# relay-shield.net
KiCad netlist of a schematic drawn in EAGLE
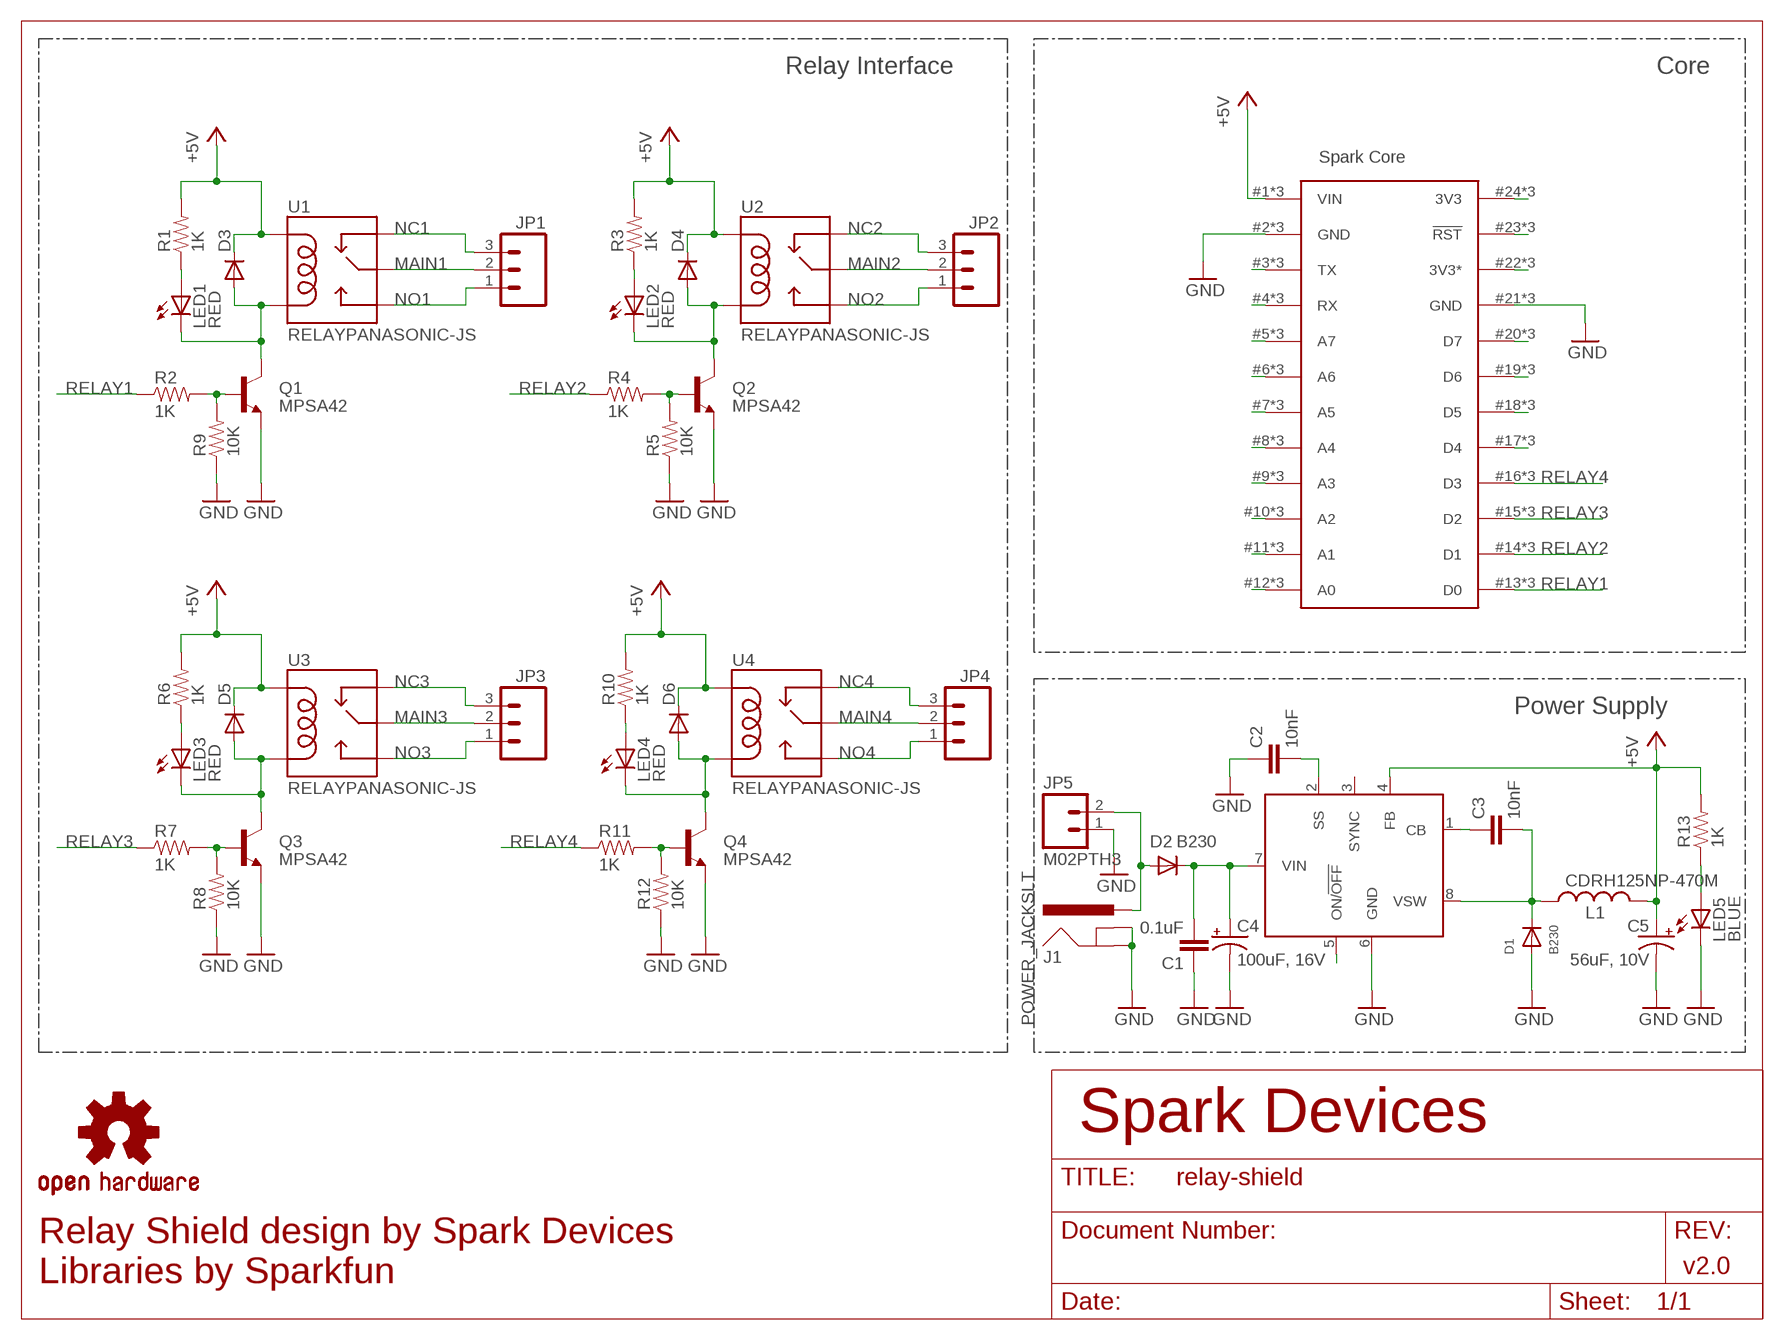
[diagram p0: schematic, sheet 1]

(export (version "E")
  (design (tool "Eeschema 10.0.6"))
  (components
    (comp (ref "C1")
      (value "0.1uF")
      (footprint "eagle-import:0603-CAP")
      (libsource (lib "eagle-import") (part "0.1UF-25V-5%(0603)"))
    )
    (comp (ref "C2")
      (value "10nF")
      (footprint "eagle-import:0603-CAP")
      (libsource (lib "eagle-import") (part "CAP0603-CAP"))
    )
    (comp (ref "C3")
      (value "10nF")
      (footprint "eagle-import:0603-CAP")
      (libsource (lib "eagle-import") (part "CAP0603-CAP"))
    )
    (comp (ref "C4")
      (value "100uF, 16V")
      (footprint "eagle-import:PANASONIC_D")
      (libsource (lib "eagle-import") (part "CAP_POLD"))
    )
    (comp (ref "C5")
      (value "56uF, 10V")
      (footprint "eagle-import:PANASONIC_D")
      (libsource (lib "eagle-import") (part "CAP_POLD"))
    )
    (comp (ref "D1")
      (value "B230")
      (footprint "eagle-import:SMADIODE")
      (libsource (lib "eagle-import") (part "DIODESMA"))
    )
    (comp (ref "D2")
      (value "B230")
      (footprint "eagle-import:SMADIODE")
      (libsource (lib "eagle-import") (part "DIODESMA"))
    )
    (comp (ref "D3")
      (value "DIODE-SOD123")
      (footprint "eagle-import:SOD123")
      (libsource (lib "eagle-import") (part "DIODE-SOD123"))
    )
    (comp (ref "D4")
      (value "DIODE-SOD123")
      (footprint "eagle-import:SOD123")
      (libsource (lib "eagle-import") (part "DIODE-SOD123"))
    )
    (comp (ref "D5")
      (value "DIODE-SOD123")
      (footprint "eagle-import:SOD123")
      (libsource (lib "eagle-import") (part "DIODE-SOD123"))
    )
    (comp (ref "D6")
      (value "DIODE-SOD123")
      (footprint "eagle-import:SOD123")
      (libsource (lib "eagle-import") (part "DIODE-SOD123"))
    )
    (comp (ref "J1")
      (value "POWER_JACKSLT")
      (footprint "eagle-import:POWER_JACK_SLOT")
      (libsource (lib "eagle-import") (part "POWER_JACKSLT"))
    )
    (comp (ref "JP1")
      (value "M03-SCREW-5MM")
      (footprint "eagle-import:SCREWTERMINAL-5MM-3")
      (libsource (lib "eagle-import") (part "M03-SCREW-5MM"))
    )
    (comp (ref "JP2")
      (value "M03-SCREW-5MM")
      (footprint "eagle-import:SCREWTERMINAL-5MM-3")
      (libsource (lib "eagle-import") (part "M03-SCREW-5MM"))
    )
    (comp (ref "JP3")
      (value "M03-SCREW-5MM")
      (footprint "eagle-import:SCREWTERMINAL-5MM-3")
      (libsource (lib "eagle-import") (part "M03-SCREW-5MM"))
    )
    (comp (ref "JP4")
      (value "M03-SCREW-5MM")
      (footprint "eagle-import:SCREWTERMINAL-5MM-3")
      (libsource (lib "eagle-import") (part "M03-SCREW-5MM"))
    )
    (comp (ref "JP5")
      (value "M02PTH3")
      (footprint "eagle-import:1X02_LONGPADS")
      (libsource (lib "eagle-import") (part "M02PTH3"))
    )
    (comp (ref "L1")
      (value "CDRH125NP-470M")
      (footprint "eagle-import:CDRH125")
      (libsource (lib "eagle-import") (part "INDUCTORPWR"))
    )
    (comp (ref "LED1")
      (value "RED")
      (footprint "eagle-import:LED-0603")
      (libsource (lib "eagle-import") (part "LED0603"))
    )
    (comp (ref "LED2")
      (value "RED")
      (footprint "eagle-import:LED-0603")
      (libsource (lib "eagle-import") (part "LED0603"))
    )
    (comp (ref "LED3")
      (value "RED")
      (footprint "eagle-import:LED-0603")
      (libsource (lib "eagle-import") (part "LED0603"))
    )
    (comp (ref "LED4")
      (value "RED")
      (footprint "eagle-import:LED-0603")
      (libsource (lib "eagle-import") (part "LED0603"))
    )
    (comp (ref "LED5")
      (value "BLUE")
      (footprint "eagle-import:LED-0603")
      (libsource (lib "eagle-import") (part "LED0603"))
    )
    (comp (ref "LOGO1")
      (value "OSHW-LOGOM")
      (footprint "eagle-import:OSHW-LOGO-M")
      (libsource (lib "eagle-import") (part "OSHW-LOGOM"))
    )
    (comp (ref "Q1")
      (value "MPSA42")
      (footprint "eagle-import:SOT23")
      (libsource (lib "eagle-import") (part "TRANSISTOR_NPNMPSA42"))
    )
    (comp (ref "Q2")
      (value "MPSA42")
      (footprint "eagle-import:SOT23")
      (libsource (lib "eagle-import") (part "TRANSISTOR_NPNMPSA42"))
    )
    (comp (ref "Q3")
      (value "MPSA42")
      (footprint "eagle-import:SOT23")
      (libsource (lib "eagle-import") (part "TRANSISTOR_NPNMPSA42"))
    )
    (comp (ref "Q4")
      (value "MPSA42")
      (footprint "eagle-import:SOT23")
      (libsource (lib "eagle-import") (part "TRANSISTOR_NPNMPSA42"))
    )
    (comp (ref "R1")
      (value "1K")
      (footprint "eagle-import:0603-RES")
      (libsource (lib "eagle-import") (part "RESISTOR0603-RES"))
    )
    (comp (ref "R2")
      (value "1K")
      (footprint "eagle-import:0603-RES")
      (libsource (lib "eagle-import") (part "RESISTOR0603-RES"))
    )
    (comp (ref "R3")
      (value "1K")
      (footprint "eagle-import:0603-RES")
      (libsource (lib "eagle-import") (part "RESISTOR0603-RES"))
    )
    (comp (ref "R4")
      (value "1K")
      (footprint "eagle-import:0603-RES")
      (libsource (lib "eagle-import") (part "RESISTOR0603-RES"))
    )
    (comp (ref "R5")
      (value "10K")
      (footprint "eagle-import:0603-RES")
      (libsource (lib "eagle-import") (part "RESISTOR0603-RES"))
    )
    (comp (ref "R6")
      (value "1K")
      (footprint "eagle-import:0603-RES")
      (libsource (lib "eagle-import") (part "RESISTOR0603-RES"))
    )
    (comp (ref "R7")
      (value "1K")
      (footprint "eagle-import:0603-RES")
      (libsource (lib "eagle-import") (part "RESISTOR0603-RES"))
    )
    (comp (ref "R8")
      (value "10K")
      (footprint "eagle-import:0603-RES")
      (libsource (lib "eagle-import") (part "RESISTOR0603-RES"))
    )
    (comp (ref "R9")
      (value "10K")
      (footprint "eagle-import:0603-RES")
      (libsource (lib "eagle-import") (part "RESISTOR0603-RES"))
    )
    (comp (ref "R10")
      (value "1K")
      (footprint "eagle-import:0603-RES")
      (libsource (lib "eagle-import") (part "RESISTOR0603-RES"))
    )
    (comp (ref "R11")
      (value "1K")
      (footprint "eagle-import:0603-RES")
      (libsource (lib "eagle-import") (part "RESISTOR0603-RES"))
    )
    (comp (ref "R12")
      (value "10K")
      (footprint "eagle-import:0603-RES")
      (libsource (lib "eagle-import") (part "RESISTOR0603-RES"))
    )
    (comp (ref "R13")
      (value "1K")
      (footprint "eagle-import:0603-RES")
      (libsource (lib "eagle-import") (part "RESISTOR0603-RES"))
    )
    (comp (ref "U$1")
      (value "SPARK_CORE")
      (footprint "eagle-import:SPARK_CORE_STACKABLE")
      (libsource (lib "eagle-import") (part "SPARK_CORE"))
    )
    (comp (ref "U1")
      (value "RELAYPANASONIC-JS")
      (footprint "eagle-import:JS1-5V-F")
      (libsource (lib "eagle-import") (part "RELAYPANASONIC-JS"))
    )
    (comp (ref "U2")
      (value "RELAYPANASONIC-JS")
      (footprint "eagle-import:JS1-5V-F")
      (libsource (lib "eagle-import") (part "RELAYPANASONIC-JS"))
    )
    (comp (ref "U3")
      (value "RELAYPANASONIC-JS")
      (footprint "eagle-import:JS1-5V-F")
      (libsource (lib "eagle-import") (part "RELAYPANASONIC-JS"))
    )
    (comp (ref "U4")
      (value "RELAYPANASONIC-JS")
      (footprint "eagle-import:JS1-5V-F")
      (libsource (lib "eagle-import") (part "RELAYPANASONIC-JS"))
    )
    (comp (ref "U5")
      (value "LM2672")
      (footprint "eagle-import:SO08")
      (libsource (lib "eagle-import") (part "LM2672"))
    )
  )
  (nets
    (net (code "1") (name "+5V") (class "Default")
      (node (ref "C5") (pin "+") (pinfunction "+_+") (pintype "passive"))
      (node (ref "D3") (pin "C") (pinfunction "C_C") (pintype "passive"))
      (node (ref "D4") (pin "C") (pinfunction "C_C") (pintype "passive"))
      (node (ref "D5") (pin "C") (pinfunction "C_C") (pintype "passive"))
      (node (ref "D6") (pin "C") (pinfunction "C_C") (pintype "passive"))
      (node (ref "L1") (pin "2") (pinfunction "2_2") (pintype "passive"))
      (node (ref "R1") (pin "2") (pinfunction "2_2") (pintype "passive"))
      (node (ref "R10") (pin "2") (pinfunction "2_2") (pintype "passive"))
      (node (ref "R13") (pin "2") (pinfunction "2_2") (pintype "passive"))
      (node (ref "R3") (pin "2") (pinfunction "2_2") (pintype "passive"))
      (node (ref "R6") (pin "2") (pinfunction "2_2") (pintype "passive"))
      (node (ref "U$1") (pin "#1") (pinfunction "VIN_#1") (pintype "power_in"))
      (node (ref "U$1") (pin "1") (pinfunction "VIN_1") (pintype "power_in"))
      (node (ref "U$1") (pin "@1") (pinfunction "VIN_@1") (pintype "power_in"))
      (node (ref "U1") (pin "COIL1") (pinfunction "COIL1_COIL1") (pintype "bidirectional"))
      (node (ref "U2") (pin "COIL1") (pinfunction "COIL1_COIL1") (pintype "bidirectional"))
      (node (ref "U3") (pin "COIL1") (pinfunction "COIL1_COIL1") (pintype "bidirectional"))
      (node (ref "U4") (pin "COIL1") (pinfunction "COIL1_COIL1") (pintype "bidirectional"))
      (node (ref "U5") (pin "4") (pinfunction "FB_4") (pintype "bidirectional"))
    )
    (net (code "2") (name "/MAIN1") (class "Default")
      (node (ref "JP1") (pin "2") (pinfunction "2_2") (pintype "passive"))
      (node (ref "U1") (pin "COMMON") (pinfunction "MAIN_COMMON") (pintype "bidirectional"))
    )
    (net (code "3") (name "/MAIN2") (class "Default")
      (node (ref "JP2") (pin "2") (pinfunction "2_2") (pintype "passive"))
      (node (ref "U2") (pin "COMMON") (pinfunction "MAIN_COMMON") (pintype "bidirectional"))
    )
    (net (code "4") (name "/MAIN3") (class "Default")
      (node (ref "JP3") (pin "2") (pinfunction "2_2") (pintype "passive"))
      (node (ref "U3") (pin "COMMON") (pinfunction "MAIN_COMMON") (pintype "bidirectional"))
    )
    (net (code "5") (name "/MAIN4") (class "Default")
      (node (ref "JP4") (pin "2") (pinfunction "2_2") (pintype "passive"))
      (node (ref "U4") (pin "COMMON") (pinfunction "MAIN_COMMON") (pintype "bidirectional"))
    )
    (net (code "6") (name "/NC1") (class "Default")
      (node (ref "JP1") (pin "3") (pinfunction "3_3") (pintype "passive"))
      (node (ref "U1") (pin "CLOSED") (pinfunction "NC_CLOSED") (pintype "bidirectional"))
    )
    (net (code "7") (name "/NC2") (class "Default")
      (node (ref "JP2") (pin "3") (pinfunction "3_3") (pintype "passive"))
      (node (ref "U2") (pin "CLOSED") (pinfunction "NC_CLOSED") (pintype "bidirectional"))
    )
    (net (code "8") (name "/NC3") (class "Default")
      (node (ref "JP3") (pin "3") (pinfunction "3_3") (pintype "passive"))
      (node (ref "U3") (pin "CLOSED") (pinfunction "NC_CLOSED") (pintype "bidirectional"))
    )
    (net (code "9") (name "/NC4") (class "Default")
      (node (ref "JP4") (pin "3") (pinfunction "3_3") (pintype "passive"))
      (node (ref "U4") (pin "CLOSED") (pinfunction "NC_CLOSED") (pintype "bidirectional"))
    )
    (net (code "10") (name "/NO1") (class "Default")
      (node (ref "JP1") (pin "1") (pinfunction "1_1") (pintype "passive"))
      (node (ref "U1") (pin "OPEN") (pinfunction "NO_OPEN") (pintype "bidirectional"))
    )
    (net (code "11") (name "/NO2") (class "Default")
      (node (ref "JP2") (pin "1") (pinfunction "1_1") (pintype "passive"))
      (node (ref "U2") (pin "OPEN") (pinfunction "NO_OPEN") (pintype "bidirectional"))
    )
    (net (code "12") (name "/NO3") (class "Default")
      (node (ref "JP3") (pin "1") (pinfunction "1_1") (pintype "passive"))
      (node (ref "U3") (pin "OPEN") (pinfunction "NO_OPEN") (pintype "bidirectional"))
    )
    (net (code "13") (name "/NO4") (class "Default")
      (node (ref "JP4") (pin "1") (pinfunction "1_1") (pintype "passive"))
      (node (ref "U4") (pin "OPEN") (pinfunction "NO_OPEN") (pintype "bidirectional"))
    )
    (net (code "14") (name "/RELAY1") (class "Default")
      (node (ref "R2") (pin "1") (pinfunction "1_1") (pintype "passive"))
      (node (ref "U$1") (pin "#13") (pinfunction "D0_#13") (pintype "bidirectional"))
      (node (ref "U$1") (pin "13") (pinfunction "D0_13") (pintype "bidirectional"))
      (node (ref "U$1") (pin "@13") (pinfunction "D0_@13") (pintype "bidirectional"))
    )
    (net (code "15") (name "/RELAY2") (class "Default")
      (node (ref "R4") (pin "1") (pinfunction "1_1") (pintype "passive"))
      (node (ref "U$1") (pin "#14") (pinfunction "D1_#14") (pintype "bidirectional"))
      (node (ref "U$1") (pin "14") (pinfunction "D1_14") (pintype "bidirectional"))
      (node (ref "U$1") (pin "@14") (pinfunction "D1_@14") (pintype "bidirectional"))
    )
    (net (code "16") (name "/RELAY3") (class "Default")
      (node (ref "R7") (pin "1") (pinfunction "1_1") (pintype "passive"))
      (node (ref "U$1") (pin "#15") (pinfunction "D2_#15") (pintype "bidirectional"))
      (node (ref "U$1") (pin "15") (pinfunction "D2_15") (pintype "bidirectional"))
      (node (ref "U$1") (pin "@15") (pinfunction "D2_@15") (pintype "bidirectional"))
    )
    (net (code "17") (name "/RELAY4") (class "Default")
      (node (ref "R11") (pin "1") (pinfunction "1_1") (pintype "passive"))
      (node (ref "U$1") (pin "#16") (pinfunction "D3_#16") (pintype "bidirectional"))
      (node (ref "U$1") (pin "16") (pinfunction "D3_16") (pintype "bidirectional"))
      (node (ref "U$1") (pin "@16") (pinfunction "D3_@16") (pintype "bidirectional"))
    )
    (net (code "18") (name "GND") (class "Default")
      (node (ref "C1") (pin "1") (pinfunction "1_1") (pintype "passive"))
      (node (ref "C2") (pin "1") (pinfunction "1_1") (pintype "passive"))
      (node (ref "C4") (pin "-") (pinfunction "-_-") (pintype "passive"))
      (node (ref "C5") (pin "-") (pinfunction "-_-") (pintype "passive"))
      (node (ref "D1") (pin "A") (pinfunction "A_A") (pintype "passive"))
      (node (ref "J1") (pin "GND@1") (pinfunction "GNDBREAK_GND@1") (pintype "bidirectional"))
      (node (ref "J1") (pin "GND@2") (pinfunction "GND_GND@2") (pintype "bidirectional"))
      (node (ref "JP5") (pin "1") (pinfunction "1_1") (pintype "passive"))
      (node (ref "LED5") (pin "C") (pinfunction "C_C") (pintype "passive"))
      (node (ref "Q1") (pin "2") (pinfunction "E_2") (pintype "passive"))
      (node (ref "Q2") (pin "2") (pinfunction "E_2") (pintype "passive"))
      (node (ref "Q3") (pin "2") (pinfunction "E_2") (pintype "passive"))
      (node (ref "Q4") (pin "2") (pinfunction "E_2") (pintype "passive"))
      (node (ref "R12") (pin "1") (pinfunction "1_1") (pintype "passive"))
      (node (ref "R5") (pin "1") (pinfunction "1_1") (pintype "passive"))
      (node (ref "R8") (pin "1") (pinfunction "1_1") (pintype "passive"))
      (node (ref "R9") (pin "1") (pinfunction "1_1") (pintype "passive"))
      (node (ref "U$1") (pin "#2") (pinfunction "GND_#2") (pintype "power_in"))
      (node (ref "U$1") (pin "#21") (pinfunction "GND_#21") (pintype "power_in"))
      (node (ref "U$1") (pin "2") (pinfunction "GND_2") (pintype "power_in"))
      (node (ref "U$1") (pin "21") (pinfunction "GND_21") (pintype "power_in"))
      (node (ref "U$1") (pin "@2") (pinfunction "GND_@2") (pintype "power_in"))
      (node (ref "U$1") (pin "@21") (pinfunction "GND_@21") (pintype "power_in"))
      (node (ref "U5") (pin "6") (pinfunction "GND_6") (pintype "power_in"))
    )
    (net (code "19") (name "Net-(D2-PadA)") (class "Default")
      (node (ref "D2") (pin "A") (pinfunction "A_A") (pintype "passive"))
      (node (ref "J1") (pin "PWR") (pinfunction "PWR_PWR") (pintype "bidirectional"))
      (node (ref "JP5") (pin "2") (pinfunction "2_2") (pintype "passive"))
    )
    (net (code "20") (name "Net-(LED1-PadA)") (class "Default")
      (node (ref "LED1") (pin "A") (pinfunction "A_A") (pintype "passive"))
      (node (ref "R1") (pin "1") (pinfunction "1_1") (pintype "passive"))
    )
    (net (code "21") (name "Net-(LED2-PadA)") (class "Default")
      (node (ref "LED2") (pin "A") (pinfunction "A_A") (pintype "passive"))
      (node (ref "R3") (pin "1") (pinfunction "1_1") (pintype "passive"))
    )
    (net (code "22") (name "Net-(LED3-PadA)") (class "Default")
      (node (ref "LED3") (pin "A") (pinfunction "A_A") (pintype "passive"))
      (node (ref "R6") (pin "1") (pinfunction "1_1") (pintype "passive"))
    )
    (net (code "23") (name "Net-(LED4-PadA)") (class "Default")
      (node (ref "LED4") (pin "A") (pinfunction "A_A") (pintype "passive"))
      (node (ref "R10") (pin "1") (pinfunction "1_1") (pintype "passive"))
    )
    (net (code "24") (name "Net-(LED5-PadA)") (class "Default")
      (node (ref "LED5") (pin "A") (pinfunction "A_A") (pintype "passive"))
      (node (ref "R13") (pin "1") (pinfunction "1_1") (pintype "passive"))
    )
    (net (code "25") (name "Net-(Q1-B)") (class "Default")
      (node (ref "Q1") (pin "1") (pinfunction "B_1") (pintype "passive"))
      (node (ref "R2") (pin "2") (pinfunction "2_2") (pintype "passive"))
      (node (ref "R9") (pin "2") (pinfunction "2_2") (pintype "passive"))
    )
    (net (code "26") (name "Net-(Q1-C)") (class "Default")
      (node (ref "D3") (pin "A") (pinfunction "A_A") (pintype "passive"))
      (node (ref "LED1") (pin "C") (pinfunction "C_C") (pintype "passive"))
      (node (ref "Q1") (pin "3") (pinfunction "C_3") (pintype "passive"))
      (node (ref "U1") (pin "COIL2") (pinfunction "COIL2_COIL2") (pintype "bidirectional"))
    )
    (net (code "27") (name "Net-(Q2-B)") (class "Default")
      (node (ref "Q2") (pin "1") (pinfunction "B_1") (pintype "passive"))
      (node (ref "R4") (pin "2") (pinfunction "2_2") (pintype "passive"))
      (node (ref "R5") (pin "2") (pinfunction "2_2") (pintype "passive"))
    )
    (net (code "28") (name "Net-(Q2-C)") (class "Default")
      (node (ref "D4") (pin "A") (pinfunction "A_A") (pintype "passive"))
      (node (ref "LED2") (pin "C") (pinfunction "C_C") (pintype "passive"))
      (node (ref "Q2") (pin "3") (pinfunction "C_3") (pintype "passive"))
      (node (ref "U2") (pin "COIL2") (pinfunction "COIL2_COIL2") (pintype "bidirectional"))
    )
    (net (code "29") (name "Net-(Q3-B)") (class "Default")
      (node (ref "Q3") (pin "1") (pinfunction "B_1") (pintype "passive"))
      (node (ref "R7") (pin "2") (pinfunction "2_2") (pintype "passive"))
      (node (ref "R8") (pin "2") (pinfunction "2_2") (pintype "passive"))
    )
    (net (code "30") (name "Net-(Q3-C)") (class "Default")
      (node (ref "D5") (pin "A") (pinfunction "A_A") (pintype "passive"))
      (node (ref "LED3") (pin "C") (pinfunction "C_C") (pintype "passive"))
      (node (ref "Q3") (pin "3") (pinfunction "C_3") (pintype "passive"))
      (node (ref "U3") (pin "COIL2") (pinfunction "COIL2_COIL2") (pintype "bidirectional"))
    )
    (net (code "31") (name "Net-(Q4-B)") (class "Default")
      (node (ref "Q4") (pin "1") (pinfunction "B_1") (pintype "passive"))
      (node (ref "R11") (pin "2") (pinfunction "2_2") (pintype "passive"))
      (node (ref "R12") (pin "2") (pinfunction "2_2") (pintype "passive"))
    )
    (net (code "32") (name "Net-(Q4-C)") (class "Default")
      (node (ref "D6") (pin "A") (pinfunction "A_A") (pintype "passive"))
      (node (ref "LED4") (pin "C") (pinfunction "C_C") (pintype "passive"))
      (node (ref "Q4") (pin "3") (pinfunction "C_3") (pintype "passive"))
      (node (ref "U4") (pin "COIL2") (pinfunction "COIL2_COIL2") (pintype "bidirectional"))
    )
    (net (code "33") (name "Net-(U$1-3V3*-Pad#22)") (class "Default")
      (node (ref "U$1") (pin "#22") (pinfunction "3V3*_#22") (pintype "power_in"))
      (node (ref "U$1") (pin "22") (pinfunction "3V3*_22") (pintype "power_in"))
      (node (ref "U$1") (pin "@22") (pinfunction "3V3*_@22") (pintype "power_in"))
    )
    (net (code "34") (name "Net-(U$1-3V3-Pad#24)") (class "Default")
      (node (ref "U$1") (pin "#24") (pinfunction "3V3_#24") (pintype "power_in"))
      (node (ref "U$1") (pin "24") (pinfunction "3V3_24") (pintype "power_in"))
      (node (ref "U$1") (pin "@24") (pinfunction "3V3_@24") (pintype "power_in"))
    )
    (net (code "35") (name "Net-(U$1-A0-Pad#12)") (class "Default")
      (node (ref "U$1") (pin "#12") (pinfunction "A0_#12") (pintype "bidirectional"))
      (node (ref "U$1") (pin "12") (pinfunction "A0_12") (pintype "bidirectional"))
      (node (ref "U$1") (pin "@12") (pinfunction "A0_@12") (pintype "bidirectional"))
    )
    (net (code "36") (name "Net-(U$1-A1-Pad#11)") (class "Default")
      (node (ref "U$1") (pin "#11") (pinfunction "A1_#11") (pintype "bidirectional"))
      (node (ref "U$1") (pin "11") (pinfunction "A1_11") (pintype "bidirectional"))
      (node (ref "U$1") (pin "@11") (pinfunction "A1_@11") (pintype "bidirectional"))
    )
    (net (code "37") (name "Net-(U$1-A2-Pad#10)") (class "Default")
      (node (ref "U$1") (pin "#10") (pinfunction "A2_#10") (pintype "bidirectional"))
      (node (ref "U$1") (pin "10") (pinfunction "A2_10") (pintype "bidirectional"))
      (node (ref "U$1") (pin "@10") (pinfunction "A2_@10") (pintype "bidirectional"))
    )
    (net (code "38") (name "Net-(U$1-A3-Pad#9)") (class "Default")
      (node (ref "U$1") (pin "#9") (pinfunction "A3_#9") (pintype "bidirectional"))
      (node (ref "U$1") (pin "9") (pinfunction "A3_9") (pintype "bidirectional"))
      (node (ref "U$1") (pin "@9") (pinfunction "A3_@9") (pintype "bidirectional"))
    )
    (net (code "39") (name "Net-(U$1-A4-Pad#8)") (class "Default")
      (node (ref "U$1") (pin "#8") (pinfunction "A4_#8") (pintype "bidirectional"))
      (node (ref "U$1") (pin "8") (pinfunction "A4_8") (pintype "bidirectional"))
      (node (ref "U$1") (pin "@8") (pinfunction "A4_@8") (pintype "bidirectional"))
    )
    (net (code "40") (name "Net-(U$1-A5-Pad#7)") (class "Default")
      (node (ref "U$1") (pin "#7") (pinfunction "A5_#7") (pintype "bidirectional"))
      (node (ref "U$1") (pin "7") (pinfunction "A5_7") (pintype "bidirectional"))
      (node (ref "U$1") (pin "@7") (pinfunction "A5_@7") (pintype "bidirectional"))
    )
    (net (code "41") (name "Net-(U$1-A6-Pad#6)") (class "Default")
      (node (ref "U$1") (pin "#6") (pinfunction "A6_#6") (pintype "bidirectional"))
      (node (ref "U$1") (pin "6") (pinfunction "A6_6") (pintype "bidirectional"))
      (node (ref "U$1") (pin "@6") (pinfunction "A6_@6") (pintype "bidirectional"))
    )
    (net (code "42") (name "Net-(U$1-A7-Pad#5)") (class "Default")
      (node (ref "U$1") (pin "#5") (pinfunction "A7_#5") (pintype "bidirectional"))
      (node (ref "U$1") (pin "5") (pinfunction "A7_5") (pintype "bidirectional"))
      (node (ref "U$1") (pin "@5") (pinfunction "A7_@5") (pintype "bidirectional"))
    )
    (net (code "43") (name "Net-(U$1-D4-Pad#17)") (class "Default")
      (node (ref "U$1") (pin "#17") (pinfunction "D4_#17") (pintype "bidirectional"))
      (node (ref "U$1") (pin "17") (pinfunction "D4_17") (pintype "bidirectional"))
      (node (ref "U$1") (pin "@17") (pinfunction "D4_@17") (pintype "bidirectional"))
    )
    (net (code "44") (name "Net-(U$1-D5-Pad#18)") (class "Default")
      (node (ref "U$1") (pin "#18") (pinfunction "D5_#18") (pintype "bidirectional"))
      (node (ref "U$1") (pin "18") (pinfunction "D5_18") (pintype "bidirectional"))
      (node (ref "U$1") (pin "@18") (pinfunction "D5_@18") (pintype "bidirectional"))
    )
    (net (code "45") (name "Net-(U$1-D6-Pad#19)") (class "Default")
      (node (ref "U$1") (pin "#19") (pinfunction "D6_#19") (pintype "bidirectional"))
      (node (ref "U$1") (pin "19") (pinfunction "D6_19") (pintype "bidirectional"))
      (node (ref "U$1") (pin "@19") (pinfunction "D6_@19") (pintype "bidirectional"))
    )
    (net (code "46") (name "Net-(U$1-D7-Pad#20)") (class "Default")
      (node (ref "U$1") (pin "#20") (pinfunction "D7_#20") (pintype "bidirectional"))
      (node (ref "U$1") (pin "20") (pinfunction "D7_20") (pintype "bidirectional"))
      (node (ref "U$1") (pin "@20") (pinfunction "D7_@20") (pintype "bidirectional"))
    )
    (net (code "47") (name "Net-(U$1-RX-Pad#4)") (class "Default")
      (node (ref "U$1") (pin "#4") (pinfunction "RX_#4") (pintype "bidirectional"))
      (node (ref "U$1") (pin "4") (pinfunction "RX_4") (pintype "bidirectional"))
      (node (ref "U$1") (pin "@4") (pinfunction "RX_@4") (pintype "bidirectional"))
    )
    (net (code "48") (name "Net-(U$1-TX-Pad#3)") (class "Default")
      (node (ref "U$1") (pin "#3") (pinfunction "TX_#3") (pintype "bidirectional"))
      (node (ref "U$1") (pin "3") (pinfunction "TX_3") (pintype "bidirectional"))
      (node (ref "U$1") (pin "@3") (pinfunction "TX_@3") (pintype "bidirectional"))
    )
    (net (code "49") (name "Net-(U$1-~{RST}-Pad#23)") (class "Default")
      (node (ref "U$1") (pin "#23") (pinfunction "~{RST}_#23") (pintype "bidirectional"))
      (node (ref "U$1") (pin "23") (pinfunction "~{RST}_23") (pintype "bidirectional"))
      (node (ref "U$1") (pin "@23") (pinfunction "~{RST}_@23") (pintype "bidirectional"))
    )
    (net (code "50") (name "Net-(U5-CB)") (class "Default")
      (node (ref "C3") (pin "1") (pinfunction "1_1") (pintype "passive"))
      (node (ref "U5") (pin "1") (pinfunction "CB_1") (pintype "bidirectional"))
    )
    (net (code "51") (name "Net-(U5-SS)") (class "Default")
      (node (ref "C2") (pin "2") (pinfunction "2_2") (pintype "passive"))
      (node (ref "U5") (pin "2") (pinfunction "SS_2") (pintype "bidirectional"))
    )
    (net (code "52") (name "Net-(U5-VIN)") (class "Default")
      (node (ref "C1") (pin "2") (pinfunction "2_2") (pintype "passive"))
      (node (ref "C4") (pin "+") (pinfunction "+_+") (pintype "passive"))
      (node (ref "D2") (pin "C") (pinfunction "C_C") (pintype "passive"))
      (node (ref "U5") (pin "7") (pinfunction "VIN_7") (pintype "power_in"))
    )
    (net (code "53") (name "Net-(U5-VSW)") (class "Default")
      (node (ref "C3") (pin "2") (pinfunction "2_2") (pintype "passive"))
      (node (ref "D1") (pin "C") (pinfunction "C_C") (pintype "passive"))
      (node (ref "L1") (pin "1") (pinfunction "1_1") (pintype "passive"))
      (node (ref "U5") (pin "8") (pinfunction "VSW_8") (pintype "bidirectional"))
    )
    (net (code "54") (name "unconnected-(U5-ON{slash}~{OFF}-Pad5)") (class "Default")
      (node (ref "U5") (pin "5") (pinfunction "ON/~{OFF}_5") (pintype "bidirectional"))
    )
    (net (code "55") (name "unconnected-(U5-SYNC-Pad3)") (class "Default")
      (node (ref "U5") (pin "3") (pinfunction "SYNC_3") (pintype "bidirectional"))
    )
  )
)
